# SH1_-_POWER.net
KiCad netlist of a schematic drawn in Altium Designer
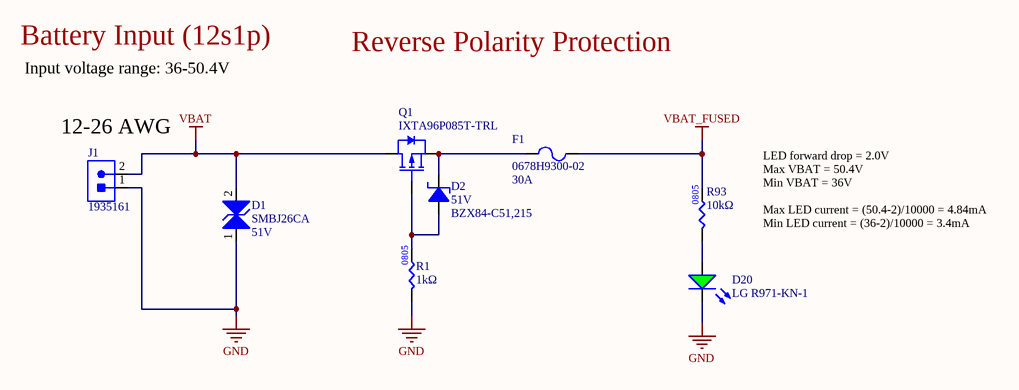
[diagram p0: SH1 - POWER.SchDoc]

(export (version "E")
  (design (tool "Eeschema 10.0.6"))
  (components
    (comp (ref "D1")
      (value "TVS_DIODE_BIDIR_51V")
      (footprint "TVS_DIODE_BIDIR_SMB")
      (description "TVS DIODE 51VWM 82.4VC DO214AA")
      (fields
        (field (name "MANUFACTURER PART NUMBER 1") "SMBJ26CA")
        (field (name "VOLTAGE - REVERSE STANDOFF (TYP)") "51V")
      )
      (libsource (lib "UWRT_Schematic_Library_2020") (part "TVS_DIODE_BIDIR_51V"))
    )
    (comp (ref "D2")
      (value "DIO_ZENER_51V")
      (footprint "SOT23-3")
      (description "DIODE ZENER 51V 250MW TO236AB")
      (fields
        (field (name "MANUFACTURER PART NUMBER 1") "BZX84-C51,215")
        (field (name "WORKING VOLTAGE") "51V")
      )
      (libsource (lib "UWRT_Schematic_Library_2020") (part "DIO_ZENER_51V"))
    )
    (comp (ref "D20")
      (value "LED_GREEN")
      (footprint "LED_0805_GREEN")
      (description "LED GREEN DIFFUSED 0805 SMD")
      (fields (field (name "MANUFACTURER PART NUMBER 1") "LG R971-KN-1"))
      (libsource (lib "UWRT_Schematic_Library_2020") (part "LED_GREEN"))
    )
    (comp (ref "F1")
      (value "FUSE_30A_3912")
      (footprint "FUSE_3912")
      (description "FUSE SMT 3912 ENH BRK 250V 30A")
      (fields
        (field (name "MANUFACTURER PART NUMBER 1") "0678H9300-02")
        (field (name "CURRENT RATING") "30A")
      )
      (libsource (lib "UWRT_Schematic_Library_2020") (part "FUSE_30A_3912"))
    )
    (comp (ref "J1")
      (value "CON_2M_TERM")
      (footprint "1935161")
      (description "TERM BLK 2POS SIDE ENTRY 5MM")
      (fields (field (name "VOLTAGE") "300V") (field (name "MANUFACTURER PART NUMBER 1") "1935161"))
      (libsource (lib "UWRT_Schematic_Library_2020") (part "CON_2M_TERM"))
    )
    (comp (ref "Q1")
      (value "PMOS_85V_96A")
      (footprint "D-PAK")
      (description "MOSFET P-CH 85V 96A TO263")
      (fields (field (name "MANUFACTURER PART NUMBER 1") "IXTA96P085T-TRL"))
      (libsource (lib "UWRT_Schematic_Library_2020") (part "PMOS_85V_96A"))
    )
    (comp (ref "R1")
      (value "1kΩ")
      (footprint "RES0805")
      (description "RES 1K OHM 1% 1/8W 0805")
      (fields (field (name "LCSC PART #") "C17513") (field (name "Comment") "RES_1kΩ_0805_1%"))
      (libsource (lib "UWRT_Schematic_Library_2020") (part "RES_1kΩ_0805_1%"))
    )
    (comp (ref "R93")
      (value "10kΩ")
      (footprint "RES0805")
      (description "RES 10K OHM 5% 1/8W 0805")
      (fields (field (name "LCSC PART #") "C17414") (field (name "Comment") "RES_10kΩ_0805_5%"))
      (libsource (lib "UWRT_Schematic_Library_2020") (part "RES_10kΩ_0805_5%"))
    )
  )
  (nets
    (net (code "1") (name "GND") (class "Default")
      (node (ref "D1") (pin "1") (pinfunction "1_1") (pintype "passive"))
      (node (ref "D20") (pin "2") (pinfunction "K_2") (pintype "passive"))
      (node (ref "J1") (pin "1") (pinfunction "1_1") (pintype "passive"))
      (node (ref "R1") (pin "1") (pinfunction "1_1") (pintype "passive"))
    )
    (net (code "2") (name "Net-(D2-Anode)") (class "Default")
      (node (ref "D2") (pin "1") (pinfunction "Anode_1") (pintype "passive"))
      (node (ref "Q1") (pin "2") (pinfunction "Gate_2") (pintype "passive"))
      (node (ref "R1") (pin "2") (pinfunction "2_2") (pintype "passive"))
    )
    (net (code "3") (name "Net-(D2-Cathode)") (class "Default")
      (node (ref "D2") (pin "3") (pinfunction "Cathode_3") (pintype "passive"))
      (node (ref "F1") (pin "1") (pinfunction "1_1") (pintype "passive"))
      (node (ref "Q1") (pin "3") (pinfunction "Source_3") (pintype "passive"))
    )
    (net (code "4") (name "Net-(D20-A)") (class "Default")
      (node (ref "D20") (pin "1") (pinfunction "A_1") (pintype "passive"))
      (node (ref "R93") (pin "1") (pinfunction "1_1") (pintype "passive"))
    )
    (net (code "5") (name "VBAT") (class "Default")
      (node (ref "D1") (pin "2") (pinfunction "2_2") (pintype "passive"))
      (node (ref "J1") (pin "2") (pinfunction "2_2") (pintype "passive"))
      (node (ref "Q1") (pin "1") (pinfunction "Drain_1") (pintype "passive"))
    )
    (net (code "6") (name "VBAT_FUSED") (class "Default")
      (node (ref "F1") (pin "2") (pinfunction "2_2") (pintype "passive"))
      (node (ref "R93") (pin "2") (pinfunction "2_2") (pintype "passive"))
    )
  )
)
